# ChristmasTree.net
KiCad netlist of a schematic drawn in Altium Designer
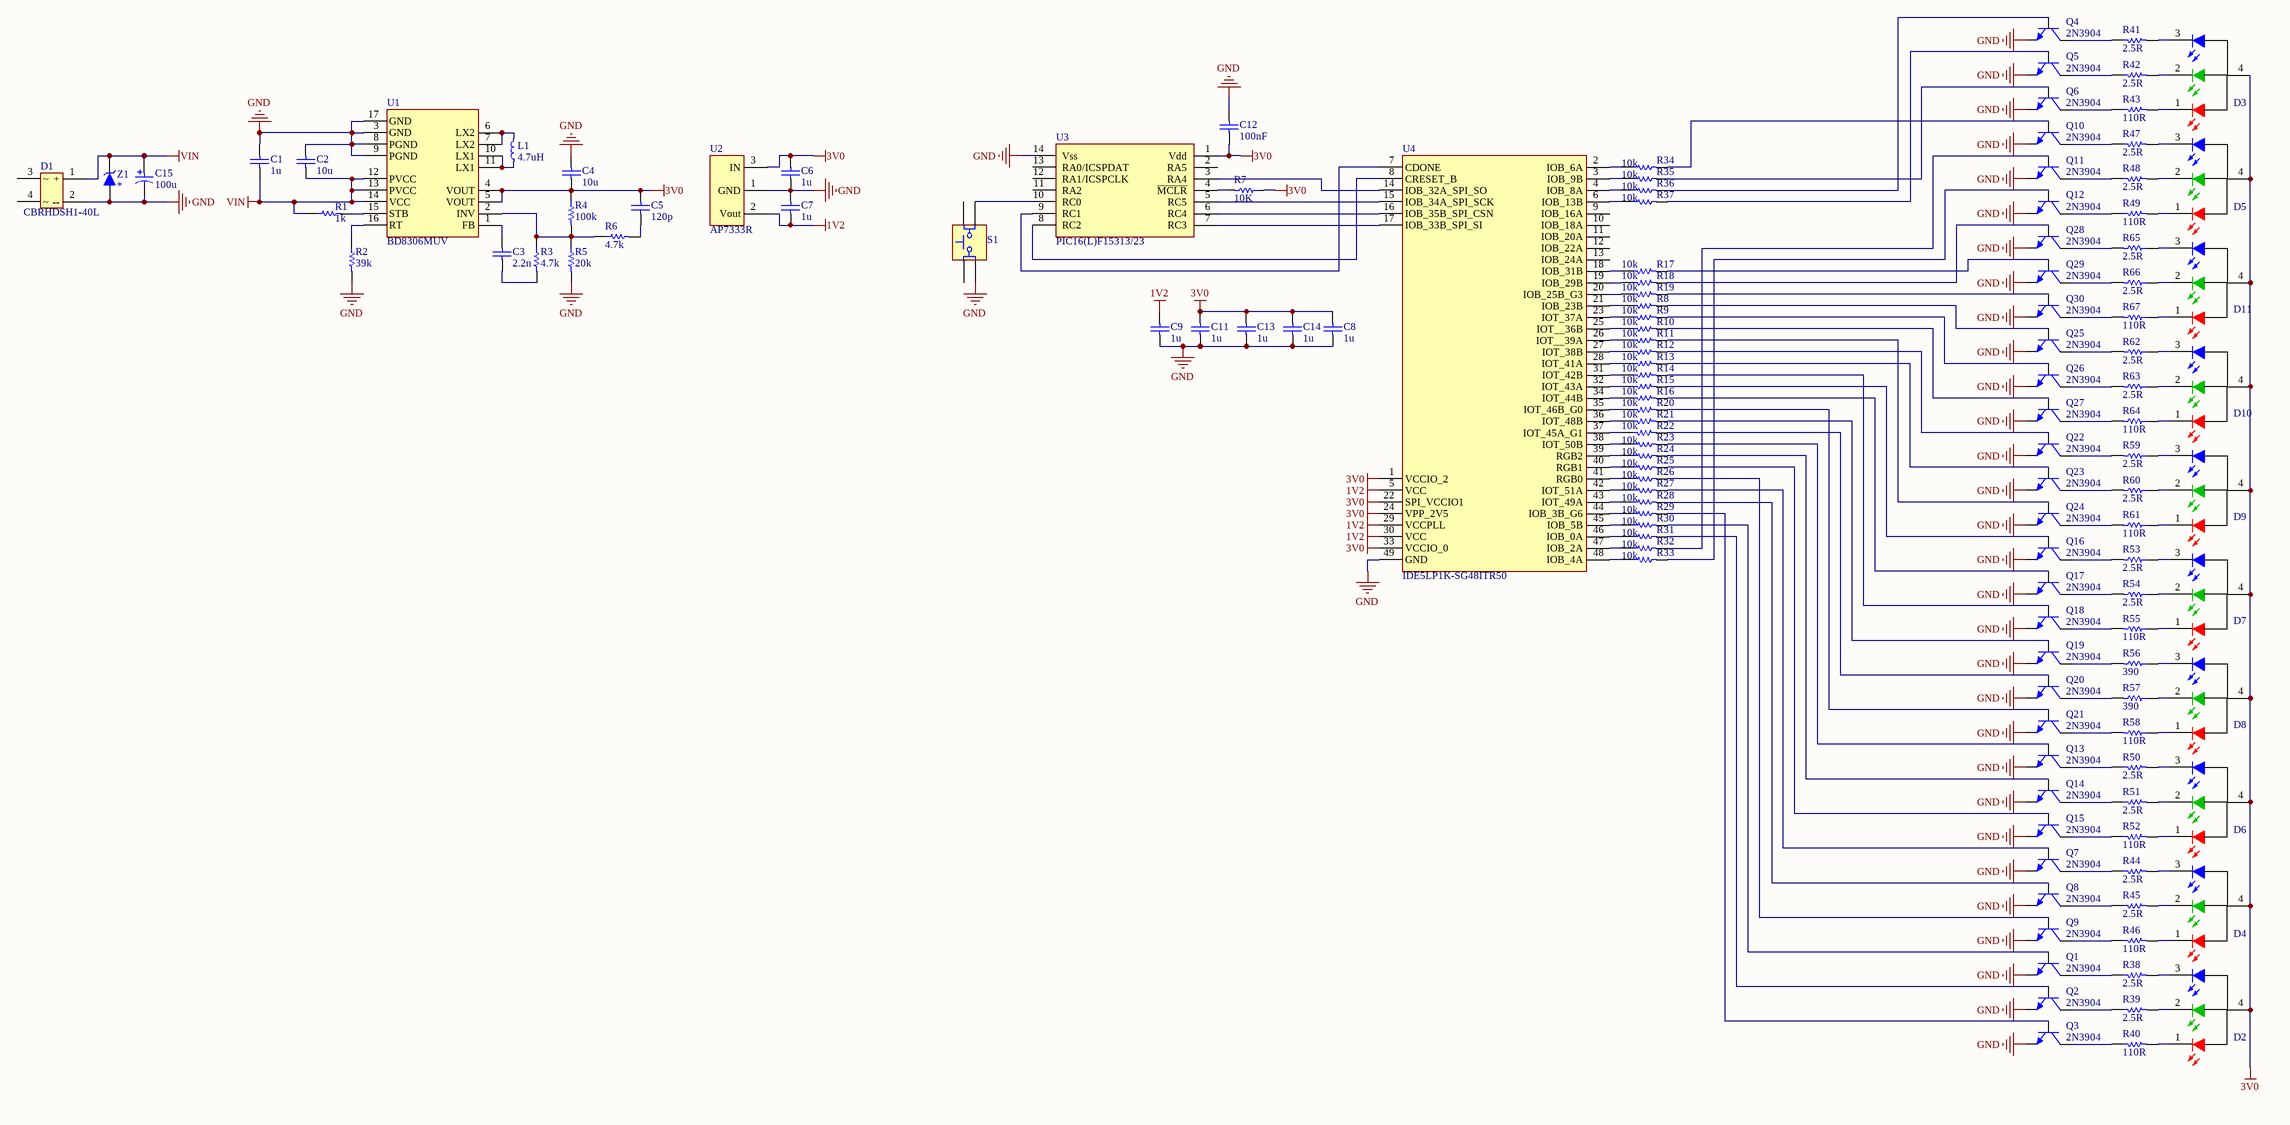
[diagram p0: ChristmasTree.SchDoc]

(export (version "E")
  (design (tool "Eeschema 10.0.6"))
  (components
    (comp (ref "C1")
      (value "1u")
      (footprint "CAP 0603_N")
      (description "CAP, CER")
      (libsource (lib "Passive Components") (part "-Cap Non-Pol"))
    )
    (comp (ref "C2")
      (value "10u")
      (footprint "CAP 0805_N")
      (description "CAP, CER")
      (libsource (lib "Passive Components") (part "-Cap Non-Pol"))
    )
    (comp (ref "C3")
      (value "2.2n")
      (footprint "CAP 0603_N")
      (description "CAP, CER")
      (libsource (lib "Passive Components") (part "-Cap Non-Pol"))
    )
    (comp (ref "C4")
      (value "10u")
      (footprint "CAP 0805_N")
      (description "CAP, CER")
      (libsource (lib "Passive Components") (part "-Cap Non-Pol"))
    )
    (comp (ref "C5")
      (value "120p")
      (footprint "CAP 0603_N")
      (description "CAP, CER")
      (libsource (lib "Passive Components") (part "-Cap Non-Pol"))
    )
    (comp (ref "C6")
      (value "1u")
      (footprint "CAP 0603_N")
      (description "CAP, CER")
      (libsource (lib "Passive Components") (part "-Cap Non-Pol"))
    )
    (comp (ref "C7")
      (value "1u")
      (footprint "CAP 0603_N")
      (description "CAP, CER")
      (libsource (lib "Passive Components") (part "-Cap Non-Pol"))
    )
    (comp (ref "C8")
      (value "1u")
      (footprint "CAP 0603_N")
      (description "CAP, CER")
      (libsource (lib "Passive Components") (part "-Cap Non-Pol"))
    )
    (comp (ref "C9")
      (value "1u")
      (footprint "CAP 0805_N")
      (description "CAP, CER")
      (libsource (lib "Passive Components") (part "-Cap Non-Pol"))
    )
    (comp (ref "C11")
      (value "1u")
      (footprint "CAP 0603_N")
      (description "CAP, CER")
      (libsource (lib "Passive Components") (part "-Cap Non-Pol"))
    )
    (comp (ref "C12")
      (value "100nF")
      (footprint "CAP 0805_N")
      (description "CAP, CER")
      (libsource (lib "Passive Components") (part "-Cap Non-Pol"))
    )
    (comp (ref "C13")
      (value "1u")
      (footprint "CAP 0603_N")
      (description "CAP, CER")
      (libsource (lib "Passive Components") (part "-Cap Non-Pol"))
    )
    (comp (ref "C14")
      (value "1u")
      (footprint "CAP 0603_N")
      (description "CAP, CER")
      (libsource (lib "Passive Components") (part "-Cap Non-Pol"))
    )
    (comp (ref "C15")
      (value "100u")
      (footprint "SMD CAP-6.3X7.7MM-A1K2")
      (description "CAP, ALUM, A1K2")
      (libsource (lib "Passive Components") (part "-Cap Aluminum"))
    )
    (comp (ref "D1")
      (value "CBRHDSH1-40L")
      (footprint "HDDIP(Rectifier)")
      (libsource (lib "A_Semi") (part "CBRHDSH1-40L"))
    )
    (comp (ref "D2")
      (value "RGB LED Common Anode")
      (footprint "LED LTST-C19HE1WT")
      (libsource (lib "Austin_Components") (part "RGB LED Common Anode"))
    )
    (comp (ref "D3")
      (value "RGB LED Common Anode")
      (footprint "LED LTST-C19HE1WT")
      (libsource (lib "Austin_Components") (part "RGB LED Common Anode"))
    )
    (comp (ref "D4")
      (value "RGB LED Common Anode")
      (footprint "LED LTST-C19HE1WT")
      (libsource (lib "Austin_Components") (part "RGB LED Common Anode"))
    )
    (comp (ref "D5")
      (value "RGB LED Common Anode")
      (footprint "LED LTST-C19HE1WT")
      (libsource (lib "Austin_Components") (part "RGB LED Common Anode"))
    )
    (comp (ref "D6")
      (value "RGB LED Common Anode")
      (footprint "LED LTST-C19HE1WT")
      (libsource (lib "Austin_Components") (part "RGB LED Common Anode"))
    )
    (comp (ref "D7")
      (value "RGB LED Common Anode")
      (footprint "LED LTST-C19HE1WT")
      (libsource (lib "Austin_Components") (part "RGB LED Common Anode"))
    )
    (comp (ref "D8")
      (value "RGB LED Common Anode")
      (footprint "LED LTST-C19HE1WT")
      (libsource (lib "Austin_Components") (part "RGB LED Common Anode"))
    )
    (comp (ref "D9")
      (value "RGB LED Common Anode")
      (footprint "LED LTST-C19HE1WT")
      (libsource (lib "Austin_Components") (part "RGB LED Common Anode"))
    )
    (comp (ref "D10")
      (value "RGB LED Common Anode")
      (footprint "LED LTST-C19HE1WT")
      (libsource (lib "Austin_Components") (part "RGB LED Common Anode"))
    )
    (comp (ref "D11")
      (value "RGB LED Common Anode")
      (footprint "LED LTST-C19HE1WT")
      (libsource (lib "Austin_Components") (part "RGB LED Common Anode"))
    )
    (comp (ref "L1")
      (value "4.7uH")
      (footprint "INDC2520X12N")
      (description "IND")
      (libsource (lib "A_Passive") (part "-Inductor"))
    )
    (comp (ref "Q1")
      (value "2N3904")
      (footprint "SOT95P245X110-3N")
      (description "NPN General Purpose Amplifier")
      (fields (field (name "PUBLISHER") "Altium Limited"))
      (libsource (lib "Austin_Components") (part "2N3904"))
    )
    (comp (ref "Q2")
      (value "2N3904")
      (footprint "SOT95P245X110-3N")
      (description "NPN General Purpose Amplifier")
      (fields (field (name "PUBLISHER") "Altium Limited"))
      (libsource (lib "Austin_Components") (part "2N3904"))
    )
    (comp (ref "Q3")
      (value "2N3904")
      (footprint "SOT95P245X110-3N")
      (description "NPN General Purpose Amplifier")
      (fields (field (name "PUBLISHER") "Altium Limited"))
      (libsource (lib "Austin_Components") (part "2N3904"))
    )
    (comp (ref "Q4")
      (value "2N3904")
      (footprint "SOT95P245X110-3N")
      (description "NPN General Purpose Amplifier")
      (fields (field (name "PUBLISHER") "Altium Limited"))
      (libsource (lib "Austin_Components") (part "2N3904"))
    )
    (comp (ref "Q5")
      (value "2N3904")
      (footprint "SOT95P245X110-3N")
      (description "NPN General Purpose Amplifier")
      (fields (field (name "PUBLISHER") "Altium Limited"))
      (libsource (lib "Austin_Components") (part "2N3904"))
    )
    (comp (ref "Q6")
      (value "2N3904")
      (footprint "SOT95P245X110-3N")
      (description "NPN General Purpose Amplifier")
      (fields (field (name "PUBLISHER") "Altium Limited"))
      (libsource (lib "Austin_Components") (part "2N3904"))
    )
    (comp (ref "Q7")
      (value "2N3904")
      (footprint "SOT95P245X110-3N")
      (description "NPN General Purpose Amplifier")
      (fields (field (name "PUBLISHER") "Altium Limited"))
      (libsource (lib "Austin_Components") (part "2N3904"))
    )
    (comp (ref "Q8")
      (value "2N3904")
      (footprint "SOT95P245X110-3N")
      (description "NPN General Purpose Amplifier")
      (fields (field (name "PUBLISHER") "Altium Limited"))
      (libsource (lib "Austin_Components") (part "2N3904"))
    )
    (comp (ref "Q9")
      (value "2N3904")
      (footprint "SOT95P245X110-3N")
      (description "NPN General Purpose Amplifier")
      (fields (field (name "PUBLISHER") "Altium Limited"))
      (libsource (lib "Austin_Components") (part "2N3904"))
    )
    (comp (ref "Q10")
      (value "2N3904")
      (footprint "SOT95P245X110-3N")
      (description "NPN General Purpose Amplifier")
      (fields (field (name "PUBLISHER") "Altium Limited"))
      (libsource (lib "Austin_Components") (part "2N3904"))
    )
    (comp (ref "Q11")
      (value "2N3904")
      (footprint "SOT95P245X110-3N")
      (description "NPN General Purpose Amplifier")
      (fields (field (name "PUBLISHER") "Altium Limited"))
      (libsource (lib "Austin_Components") (part "2N3904"))
    )
    (comp (ref "Q12")
      (value "2N3904")
      (footprint "SOT95P245X110-3N")
      (description "NPN General Purpose Amplifier")
      (fields (field (name "PUBLISHER") "Altium Limited"))
      (libsource (lib "Austin_Components") (part "2N3904"))
    )
    (comp (ref "Q13")
      (value "2N3904")
      (footprint "SOT95P245X110-3N")
      (description "NPN General Purpose Amplifier")
      (fields (field (name "PUBLISHER") "Altium Limited"))
      (libsource (lib "Austin_Components") (part "2N3904"))
    )
    (comp (ref "Q14")
      (value "2N3904")
      (footprint "SOT95P245X110-3N")
      (description "NPN General Purpose Amplifier")
      (fields (field (name "PUBLISHER") "Altium Limited"))
      (libsource (lib "Austin_Components") (part "2N3904"))
    )
    (comp (ref "Q15")
      (value "2N3904")
      (footprint "SOT95P245X110-3N")
      (description "NPN General Purpose Amplifier")
      (fields (field (name "PUBLISHER") "Altium Limited"))
      (libsource (lib "Austin_Components") (part "2N3904"))
    )
    (comp (ref "Q16")
      (value "2N3904")
      (footprint "SOT95P245X110-3N")
      (description "NPN General Purpose Amplifier")
      (fields (field (name "PUBLISHER") "Altium Limited"))
      (libsource (lib "Austin_Components") (part "2N3904"))
    )
    (comp (ref "Q17")
      (value "2N3904")
      (footprint "SOT95P245X110-3N")
      (description "NPN General Purpose Amplifier")
      (fields (field (name "PUBLISHER") "Altium Limited"))
      (libsource (lib "Austin_Components") (part "2N3904"))
    )
    (comp (ref "Q18")
      (value "2N3904")
      (footprint "SOT95P245X110-3N")
      (description "NPN General Purpose Amplifier")
      (fields (field (name "PUBLISHER") "Altium Limited"))
      (libsource (lib "Austin_Components") (part "2N3904"))
    )
    (comp (ref "Q19")
      (value "2N3904")
      (footprint "SOT95P245X110-3N")
      (description "NPN General Purpose Amplifier")
      (fields (field (name "PUBLISHER") "Altium Limited"))
      (libsource (lib "Austin_Components") (part "2N3904"))
    )
    (comp (ref "Q20")
      (value "2N3904")
      (footprint "SOT95P245X110-3N")
      (description "NPN General Purpose Amplifier")
      (fields (field (name "PUBLISHER") "Altium Limited"))
      (libsource (lib "Austin_Components") (part "2N3904"))
    )
    (comp (ref "Q21")
      (value "2N3904")
      (footprint "SOT95P245X110-3N")
      (description "NPN General Purpose Amplifier")
      (fields (field (name "PUBLISHER") "Altium Limited"))
      (libsource (lib "Austin_Components") (part "2N3904"))
    )
    (comp (ref "Q22")
      (value "2N3904")
      (footprint "SOT95P245X110-3N")
      (description "NPN General Purpose Amplifier")
      (fields (field (name "PUBLISHER") "Altium Limited"))
      (libsource (lib "Austin_Components") (part "2N3904"))
    )
    (comp (ref "Q23")
      (value "2N3904")
      (footprint "SOT95P245X110-3N")
      (description "NPN General Purpose Amplifier")
      (fields (field (name "PUBLISHER") "Altium Limited"))
      (libsource (lib "Austin_Components") (part "2N3904"))
    )
    (comp (ref "Q24")
      (value "2N3904")
      (footprint "SOT95P245X110-3N")
      (description "NPN General Purpose Amplifier")
      (fields (field (name "PUBLISHER") "Altium Limited"))
      (libsource (lib "Austin_Components") (part "2N3904"))
    )
    (comp (ref "Q25")
      (value "2N3904")
      (footprint "SOT95P245X110-3N")
      (description "NPN General Purpose Amplifier")
      (fields (field (name "PUBLISHER") "Altium Limited"))
      (libsource (lib "Austin_Components") (part "2N3904"))
    )
    (comp (ref "Q26")
      (value "2N3904")
      (footprint "SOT95P245X110-3N")
      (description "NPN General Purpose Amplifier")
      (fields (field (name "PUBLISHER") "Altium Limited"))
      (libsource (lib "Austin_Components") (part "2N3904"))
    )
    (comp (ref "Q27")
      (value "2N3904")
      (footprint "SOT95P245X110-3N")
      (description "NPN General Purpose Amplifier")
      (fields (field (name "PUBLISHER") "Altium Limited"))
      (libsource (lib "Austin_Components") (part "2N3904"))
    )
    (comp (ref "Q28")
      (value "2N3904")
      (footprint "SOT95P245X110-3N")
      (description "NPN General Purpose Amplifier")
      (fields (field (name "PUBLISHER") "Altium Limited"))
      (libsource (lib "Austin_Components") (part "2N3904"))
    )
    (comp (ref "Q29")
      (value "2N3904")
      (footprint "SOT95P245X110-3N")
      (description "NPN General Purpose Amplifier")
      (fields (field (name "PUBLISHER") "Altium Limited"))
      (libsource (lib "Austin_Components") (part "2N3904"))
    )
    (comp (ref "Q30")
      (value "2N3904")
      (footprint "SOT95P245X110-3N")
      (description "NPN General Purpose Amplifier")
      (fields (field (name "PUBLISHER") "Altium Limited"))
      (libsource (lib "Austin_Components") (part "2N3904"))
    )
    (comp (ref "R1")
      (value "1k")
      (footprint "RES 0603_N")
      (description "Resistor")
      (fields (field (name "Comment") "Res") (field (name "PUBLISHER") "Altium Limited"))
      (libsource (lib "Austin_Components") (part "Res"))
    )
    (comp (ref "R2")
      (value "39k")
      (footprint "RES 0603_N")
      (description "Resistor")
      (fields (field (name "Comment") "Res") (field (name "PUBLISHER") "Altium Limited"))
      (libsource (lib "Austin_Components") (part "Res"))
    )
    (comp (ref "R3")
      (value "4.7k")
      (footprint "RES 0603_N")
      (description "Resistor")
      (fields (field (name "Comment") "Res") (field (name "PUBLISHER") "Altium Limited"))
      (libsource (lib "Austin_Components") (part "Res"))
    )
    (comp (ref "R4")
      (value "100k")
      (footprint "RES 0603_N")
      (description "Resistor")
      (fields (field (name "Comment") "Res") (field (name "PUBLISHER") "Altium Limited"))
      (libsource (lib "Austin_Components") (part "Res"))
    )
    (comp (ref "R5")
      (value "20k")
      (footprint "RES 0603_N")
      (description "Resistor")
      (fields (field (name "Comment") "Res") (field (name "PUBLISHER") "Altium Limited"))
      (libsource (lib "Austin_Components") (part "Res"))
    )
    (comp (ref "R6")
      (value "4.7k")
      (footprint "RES 0603_N")
      (description "Resistor")
      (fields (field (name "Comment") "Res") (field (name "PUBLISHER") "Altium Limited"))
      (libsource (lib "Austin_Components") (part "Res"))
    )
    (comp (ref "R7")
      (value "10K")
      (footprint "RES 0603_N")
      (description "RES, SMD")
      (libsource (lib "Passive Components") (part "-Resistor"))
    )
    (comp (ref "R8")
      (value "10k")
      (footprint "RES 0603_N")
      (description "Resistor")
      (fields (field (name "Comment") "Res") (field (name "PUBLISHER") "Altium Limited"))
      (libsource (lib "Austin_Components") (part "Res"))
    )
    (comp (ref "R9")
      (value "10k")
      (footprint "RES 0603_N")
      (description "Resistor")
      (fields (field (name "Comment") "Res") (field (name "PUBLISHER") "Altium Limited"))
      (libsource (lib "Austin_Components") (part "Res"))
    )
    (comp (ref "R10")
      (value "10k")
      (footprint "RES 0603_N")
      (description "Resistor")
      (fields (field (name "Comment") "Res") (field (name "PUBLISHER") "Altium Limited"))
      (libsource (lib "Austin_Components") (part "Res"))
    )
    (comp (ref "R11")
      (value "10k")
      (footprint "RES 0603_N")
      (description "Resistor")
      (fields (field (name "Comment") "Res") (field (name "PUBLISHER") "Altium Limited"))
      (libsource (lib "Austin_Components") (part "Res"))
    )
    (comp (ref "R12")
      (value "10k")
      (footprint "RES 0603_N")
      (description "Resistor")
      (fields (field (name "Comment") "Res") (field (name "PUBLISHER") "Altium Limited"))
      (libsource (lib "Austin_Components") (part "Res"))
    )
    (comp (ref "R13")
      (value "10k")
      (footprint "RES 0603_N")
      (description "Resistor")
      (fields (field (name "Comment") "Res") (field (name "PUBLISHER") "Altium Limited"))
      (libsource (lib "Austin_Components") (part "Res"))
    )
    (comp (ref "R14")
      (value "10k")
      (footprint "RES 0603_N")
      (description "Resistor")
      (fields (field (name "Comment") "Res") (field (name "PUBLISHER") "Altium Limited"))
      (libsource (lib "Austin_Components") (part "Res"))
    )
    (comp (ref "R15")
      (value "10k")
      (footprint "RES 0603_N")
      (description "Resistor")
      (fields (field (name "Comment") "Res") (field (name "PUBLISHER") "Altium Limited"))
      (libsource (lib "Austin_Components") (part "Res"))
    )
    (comp (ref "R16")
      (value "10k")
      (footprint "RES 0603_N")
      (description "Resistor")
      (fields (field (name "Comment") "Res") (field (name "PUBLISHER") "Altium Limited"))
      (libsource (lib "Austin_Components") (part "Res"))
    )
    (comp (ref "R17")
      (value "10k")
      (footprint "RES 0603_N")
      (description "Resistor")
      (fields (field (name "Comment") "Res") (field (name "PUBLISHER") "Altium Limited"))
      (libsource (lib "Austin_Components") (part "Res"))
    )
    (comp (ref "R18")
      (value "10k")
      (footprint "RES 0603_N")
      (description "Resistor")
      (fields (field (name "Comment") "Res") (field (name "PUBLISHER") "Altium Limited"))
      (libsource (lib "Austin_Components") (part "Res"))
    )
    (comp (ref "R19")
      (value "10k")
      (footprint "RES 0603_N")
      (description "Resistor")
      (fields (field (name "Comment") "Res") (field (name "PUBLISHER") "Altium Limited"))
      (libsource (lib "Austin_Components") (part "Res"))
    )
    (comp (ref "R20")
      (value "10k")
      (footprint "RES 0603_N")
      (description "Resistor")
      (fields (field (name "Comment") "Res") (field (name "PUBLISHER") "Altium Limited"))
      (libsource (lib "Austin_Components") (part "Res"))
    )
    (comp (ref "R21")
      (value "10k")
      (footprint "RES 0603_N")
      (description "Resistor")
      (fields (field (name "Comment") "Res") (field (name "PUBLISHER") "Altium Limited"))
      (libsource (lib "Austin_Components") (part "Res"))
    )
    (comp (ref "R22")
      (value "10k")
      (footprint "RES 0603_N")
      (description "Resistor")
      (fields (field (name "Comment") "Res") (field (name "PUBLISHER") "Altium Limited"))
      (libsource (lib "Austin_Components") (part "Res"))
    )
    (comp (ref "R23")
      (value "10k")
      (footprint "RES 0603_N")
      (description "Resistor")
      (fields (field (name "Comment") "Res") (field (name "PUBLISHER") "Altium Limited"))
      (libsource (lib "Austin_Components") (part "Res"))
    )
    (comp (ref "R24")
      (value "10k")
      (footprint "RES 0603_N")
      (description "Resistor")
      (fields (field (name "Comment") "Res") (field (name "PUBLISHER") "Altium Limited"))
      (libsource (lib "Austin_Components") (part "Res"))
    )
    (comp (ref "R25")
      (value "10k")
      (footprint "RES 0603_N")
      (description "Resistor")
      (fields (field (name "Comment") "Res") (field (name "PUBLISHER") "Altium Limited"))
      (libsource (lib "Austin_Components") (part "Res"))
    )
    (comp (ref "R26")
      (value "10k")
      (footprint "RES 0603_N")
      (description "Resistor")
      (fields (field (name "Comment") "Res") (field (name "PUBLISHER") "Altium Limited"))
      (libsource (lib "Austin_Components") (part "Res"))
    )
    (comp (ref "R27")
      (value "10k")
      (footprint "RES 0603_N")
      (description "Resistor")
      (fields (field (name "Comment") "Res") (field (name "PUBLISHER") "Altium Limited"))
      (libsource (lib "Austin_Components") (part "Res"))
    )
    (comp (ref "R28")
      (value "10k")
      (footprint "RES 0603_N")
      (description "Resistor")
      (fields (field (name "Comment") "Res") (field (name "PUBLISHER") "Altium Limited"))
      (libsource (lib "Austin_Components") (part "Res"))
    )
    (comp (ref "R29")
      (value "10k")
      (footprint "RES 0603_N")
      (description "Resistor")
      (fields (field (name "Comment") "Res") (field (name "PUBLISHER") "Altium Limited"))
      (libsource (lib "Austin_Components") (part "Res"))
    )
    (comp (ref "R30")
      (value "10k")
      (footprint "RES 0603_N")
      (description "Resistor")
      (fields (field (name "Comment") "Res") (field (name "PUBLISHER") "Altium Limited"))
      (libsource (lib "Austin_Components") (part "Res"))
    )
    (comp (ref "R31")
      (value "10k")
      (footprint "RES 0603_N")
      (description "Resistor")
      (fields (field (name "Comment") "Res") (field (name "PUBLISHER") "Altium Limited"))
      (libsource (lib "Austin_Components") (part "Res"))
    )
    (comp (ref "R32")
      (value "10k")
      (footprint "RES 0603_N")
      (description "Resistor")
      (fields (field (name "Comment") "Res") (field (name "PUBLISHER") "Altium Limited"))
      (libsource (lib "Austin_Components") (part "Res"))
    )
    (comp (ref "R33")
      (value "10k")
      (footprint "RES 0603_N")
      (description "Resistor")
      (fields (field (name "Comment") "Res") (field (name "PUBLISHER") "Altium Limited"))
      (libsource (lib "Austin_Components") (part "Res"))
    )
    (comp (ref "R34")
      (value "10k")
      (footprint "RES 0603_N")
      (description "Resistor")
      (fields (field (name "Comment") "Res") (field (name "PUBLISHER") "Altium Limited"))
      (libsource (lib "Austin_Components") (part "Res"))
    )
    (comp (ref "R35")
      (value "10k")
      (footprint "RES 0603_N")
      (description "Resistor")
      (fields (field (name "Comment") "Res") (field (name "PUBLISHER") "Altium Limited"))
      (libsource (lib "Austin_Components") (part "Res"))
    )
    (comp (ref "R36")
      (value "10k")
      (footprint "RES 0603_N")
      (description "Resistor")
      (fields (field (name "Comment") "Res") (field (name "PUBLISHER") "Altium Limited"))
      (libsource (lib "Austin_Components") (part "Res"))
    )
    (comp (ref "R37")
      (value "10k")
      (footprint "RES 0603_N")
      (description "Resistor")
      (fields (field (name "Comment") "Res") (field (name "PUBLISHER") "Altium Limited"))
      (libsource (lib "Austin_Components") (part "Res"))
    )
    (comp (ref "R38")
      (value "2.5R")
      (footprint "RES 0603_N")
      (description "Resistor")
      (fields (field (name "Comment") "Res") (field (name "PUBLISHER") "Altium Limited"))
      (libsource (lib "Austin_Components") (part "Res"))
    )
    (comp (ref "R39")
      (value "2.5R")
      (footprint "RES 0603_N")
      (description "Resistor")
      (fields (field (name "Comment") "Res") (field (name "PUBLISHER") "Altium Limited"))
      (libsource (lib "Austin_Components") (part "Res"))
    )
    (comp (ref "R40")
      (value "110R")
      (footprint "RES 0603_N")
      (description "Resistor")
      (fields (field (name "Comment") "Res") (field (name "PUBLISHER") "Altium Limited"))
      (libsource (lib "Austin_Components") (part "Res"))
    )
    (comp (ref "R41")
      (value "2.5R")
      (footprint "RES 0603_N")
      (description "Resistor")
      (fields (field (name "Comment") "Res") (field (name "PUBLISHER") "Altium Limited"))
      (libsource (lib "Austin_Components") (part "Res"))
    )
    (comp (ref "R42")
      (value "2.5R")
      (footprint "RES 0603_N")
      (description "Resistor")
      (fields (field (name "Comment") "Res") (field (name "PUBLISHER") "Altium Limited"))
      (libsource (lib "Austin_Components") (part "Res"))
    )
    (comp (ref "R43")
      (value "110R")
      (footprint "RES 0603_N")
      (description "Resistor")
      (fields (field (name "Comment") "Res") (field (name "PUBLISHER") "Altium Limited"))
      (libsource (lib "Austin_Components") (part "Res"))
    )
    (comp (ref "R44")
      (value "2.5R")
      (footprint "RES 0603_N")
      (description "Resistor")
      (fields (field (name "Comment") "Res") (field (name "PUBLISHER") "Altium Limited"))
      (libsource (lib "Austin_Components") (part "Res"))
    )
    (comp (ref "R45")
      (value "2.5R")
      (footprint "RES 0603_N")
      (description "Resistor")
      (fields (field (name "Comment") "Res") (field (name "PUBLISHER") "Altium Limited"))
      (libsource (lib "Austin_Components") (part "Res"))
    )
    (comp (ref "R46")
      (value "110R")
      (footprint "RES 0603_N")
      (description "Resistor")
      (fields (field (name "Comment") "Res") (field (name "PUBLISHER") "Altium Limited"))
      (libsource (lib "Austin_Components") (part "Res"))
    )
    (comp (ref "R47")
      (value "2.5R")
      (footprint "RES 0603_N")
      (description "Resistor")
      (fields (field (name "Comment") "Res") (field (name "PUBLISHER") "Altium Limited"))
      (libsource (lib "Austin_Components") (part "Res"))
    )
    (comp (ref "R48")
      (value "2.5R")
      (footprint "RES 0603_N")
      (description "Resistor")
      (fields (field (name "Comment") "Res") (field (name "PUBLISHER") "Altium Limited"))
      (libsource (lib "Austin_Components") (part "Res"))
    )
    (comp (ref "R49")
      (value "110R")
      (footprint "RES 0603_N")
      (description "Resistor")
      (fields (field (name "Comment") "Res") (field (name "PUBLISHER") "Altium Limited"))
      (libsource (lib "Austin_Components") (part "Res"))
    )
    (comp (ref "R50")
      (value "2.5R")
      (footprint "RES 0603_N")
      (description "Resistor")
      (fields (field (name "Comment") "Res") (field (name "PUBLISHER") "Altium Limited"))
      (libsource (lib "Austin_Components") (part "Res"))
    )
    (comp (ref "R51")
      (value "2.5R")
      (footprint "RES 0603_N")
      (description "Resistor")
      (fields (field (name "Comment") "Res") (field (name "PUBLISHER") "Altium Limited"))
      (libsource (lib "Austin_Components") (part "Res"))
    )
    (comp (ref "R52")
      (value "110R")
      (footprint "RES 0603_N")
      (description "Resistor")
      (fields (field (name "Comment") "Res") (field (name "PUBLISHER") "Altium Limited"))
      (libsource (lib "Austin_Components") (part "Res"))
    )
    (comp (ref "R53")
      (value "2.5R")
      (footprint "RES 0603_N")
      (description "Resistor")
      (fields (field (name "Comment") "Res") (field (name "PUBLISHER") "Altium Limited"))
      (libsource (lib "Austin_Components") (part "Res"))
    )
    (comp (ref "R54")
      (value "2.5R")
      (footprint "RES 0603_N")
      (description "Resistor")
      (fields (field (name "Comment") "Res") (field (name "PUBLISHER") "Altium Limited"))
      (libsource (lib "Austin_Components") (part "Res"))
    )
    (comp (ref "R55")
      (value "110R")
      (footprint "RES 0603_N")
      (description "Resistor")
      (fields (field (name "Comment") "Res") (field (name "PUBLISHER") "Altium Limited"))
      (libsource (lib "Austin_Components") (part "Res"))
    )
    (comp (ref "R56")
      (value "390")
      (footprint "RES 0603_N")
      (description "Resistor")
      (fields (field (name "Comment") "Res") (field (name "PUBLISHER") "Altium Limited"))
      (libsource (lib "Austin_Components") (part "Res"))
    )
    (comp (ref "R57")
      (value "390")
      (footprint "RES 0603_N")
      (description "Resistor")
      (fields (field (name "Comment") "Res") (field (name "PUBLISHER") "Altium Limited"))
      (libsource (lib "Austin_Components") (part "Res"))
    )
    (comp (ref "R58")
      (value "110R")
      (footprint "RES 0603_N")
      (description "Resistor")
      (fields (field (name "Comment") "Res") (field (name "PUBLISHER") "Altium Limited"))
      (libsource (lib "Austin_Components") (part "Res"))
    )
    (comp (ref "R59")
      (value "2.5R")
      (footprint "RES 0603_N")
      (description "Resistor")
      (fields (field (name "Comment") "Res") (field (name "PUBLISHER") "Altium Limited"))
      (libsource (lib "Austin_Components") (part "Res"))
    )
    (comp (ref "R60")
      (value "2.5R")
      (footprint "RES 0603_N")
      (description "Resistor")
      (fields (field (name "Comment") "Res") (field (name "PUBLISHER") "Altium Limited"))
      (libsource (lib "Austin_Components") (part "Res"))
    )
    (comp (ref "R61")
      (value "110R")
      (footprint "RES 0603_N")
      (description "Resistor")
      (fields (field (name "Comment") "Res") (field (name "PUBLISHER") "Altium Limited"))
      (libsource (lib "Austin_Components") (part "Res"))
    )
    (comp (ref "R62")
      (value "2.5R")
      (footprint "RES 0603_N")
      (description "Resistor")
      (fields (field (name "Comment") "Res") (field (name "PUBLISHER") "Altium Limited"))
      (libsource (lib "Austin_Components") (part "Res"))
    )
    (comp (ref "R63")
      (value "2.5R")
      (footprint "RES 0603_N")
      (description "Resistor")
      (fields (field (name "Comment") "Res") (field (name "PUBLISHER") "Altium Limited"))
      (libsource (lib "Austin_Components") (part "Res"))
    )
    (comp (ref "R64")
      (value "110R")
      (footprint "RES 0603_N")
      (description "Resistor")
      (fields (field (name "Comment") "Res") (field (name "PUBLISHER") "Altium Limited"))
      (libsource (lib "Austin_Components") (part "Res"))
    )
    (comp (ref "R65")
      (value "2.5R")
      (footprint "RES 0603_N")
      (description "Resistor")
      (fields (field (name "Comment") "Res") (field (name "PUBLISHER") "Altium Limited"))
      (libsource (lib "Austin_Components") (part "Res"))
    )
    (comp (ref "R66")
      (value "2.5R")
      (footprint "RES 0603_N")
      (description "Resistor")
      (fields (field (name "Comment") "Res") (field (name "PUBLISHER") "Altium Limited"))
      (libsource (lib "Austin_Components") (part "Res"))
    )
    (comp (ref "R67")
      (value "110R")
      (footprint "RES 0603_N")
      (description "Resistor")
      (fields (field (name "Comment") "Res") (field (name "PUBLISHER") "Altium Limited"))
      (libsource (lib "Austin_Components") (part "Res"))
    )
    (comp (ref "S1")
      (value "SW Tactile")
      (footprint "SW-TACT-SMD-6060")
      (description "SPST, Normally Open, Push Button")
      (libsource (lib "Electromechanical") (part "SW-NO (PTS645SM43SMTR 92 LFS)"))
    )
    (comp (ref "U1")
      (value "BD8306MUV")
      (footprint "QFN50P300X300X100_HS-17N")
      (libsource (lib "A_Semi") (part "BD8306MUV"))
    )
    (comp (ref "U2")
      (value "AP7333R")
      (footprint "SOT95P245X110-3N")
      (libsource (lib "A_Semi") (part "AP7333R"))
    )
    (comp (ref "U3")
      (value "PIC16(L)F15313/23")
      (footprint "SOIC14")
      (libsource (lib "A_Semi") (part "PIC16(L)F15313/23"))
    )
    (comp (ref "U4")
      (value "IDE5LP1K-SG48ITR50")
      (footprint "QFN50P700X700X85_HS-49M")
      (libsource (lib "A_Semi") (part "IDE5LP1K-SG48ITR50"))
    )
    (comp (ref "Z1")
      (value "*")
      (footprint "SOD-123-K1A2")
      (description "2 Pin Zener K1A2")
      (fields (field (name "ALTIUM_VALUE") "*"))
      (libsource (lib "Semiconductors") (part "-Diode Zener K1A2"))
    )
  )
  (nets
    (net (code "1") (name "1V2") (class "Default")
      (node (ref "C7") (pin "2") (pinfunction "2_2") (pintype "passive"))
      (node (ref "C9") (pin "1") (pinfunction "1_1") (pintype "passive"))
      (node (ref "U2") (pin "2") (pinfunction "Vout_2") (pintype "passive"))
      (node (ref "U4") (pin "29") (pinfunction "VCCPLL_29") (pintype "passive"))
      (node (ref "U4") (pin "30") (pinfunction "VCC_30") (pintype "passive"))
      (node (ref "U4") (pin "5") (pinfunction "VCC_5") (pintype "passive"))
    )
    (net (code "2") (name "3V0") (class "Default")
      (node (ref "C11") (pin "1") (pinfunction "1_1") (pintype "passive"))
      (node (ref "C12") (pin "1") (pinfunction "1_1") (pintype "passive"))
      (node (ref "C13") (pin "1") (pinfunction "1_1") (pintype "passive"))
      (node (ref "C14") (pin "1") (pinfunction "1_1") (pintype "passive"))
      (node (ref "C4") (pin "2") (pinfunction "2_2") (pintype "passive"))
      (node (ref "C5") (pin "2") (pinfunction "2_2") (pintype "passive"))
      (node (ref "C6") (pin "1") (pinfunction "1_1") (pintype "passive"))
      (node (ref "C8") (pin "1") (pinfunction "1_1") (pintype "passive"))
      (node (ref "D10") (pin "4") (pinfunction "A_4") (pintype "passive"))
      (node (ref "D11") (pin "4") (pinfunction "A_4") (pintype "passive"))
      (node (ref "D2") (pin "4") (pinfunction "A_4") (pintype "passive"))
      (node (ref "D3") (pin "4") (pinfunction "A_4") (pintype "passive"))
      (node (ref "D4") (pin "4") (pinfunction "A_4") (pintype "passive"))
      (node (ref "D5") (pin "4") (pinfunction "A_4") (pintype "passive"))
      (node (ref "D6") (pin "4") (pinfunction "A_4") (pintype "passive"))
      (node (ref "D7") (pin "4") (pinfunction "A_4") (pintype "passive"))
      (node (ref "D8") (pin "4") (pinfunction "A_4") (pintype "passive"))
      (node (ref "D9") (pin "4") (pinfunction "A_4") (pintype "passive"))
      (node (ref "R4") (pin "1") (pinfunction "1_1") (pintype "passive"))
      (node (ref "R7") (pin "1") (pinfunction "1_1") (pintype "passive"))
      (node (ref "U1") (pin "4") (pinfunction "VOUT_4") (pintype "passive"))
      (node (ref "U1") (pin "5") (pinfunction "VOUT_5") (pintype "passive"))
      (node (ref "U2") (pin "3") (pinfunction "IN_3") (pintype "passive"))
      (node (ref "U3") (pin "1") (pinfunction "Vdd_1") (pintype "passive"))
      (node (ref "U4") (pin "1") (pinfunction "VCCIO_2_1") (pintype "passive"))
      (node (ref "U4") (pin "22") (pinfunction "SPI_VCCIO1_22") (pintype "passive"))
      (node (ref "U4") (pin "24") (pinfunction "VPP_2V5_24") (pintype "passive"))
      (node (ref "U4") (pin "33") (pinfunction "VCCIO_0_33") (pintype "passive"))
    )
    (net (code "3") (name "GND") (class "Default")
      (node (ref "C1") (pin "2") (pinfunction "2_2") (pintype "passive"))
      (node (ref "C11") (pin "2") (pinfunction "2_2") (pintype "passive"))
      (node (ref "C12") (pin "2") (pinfunction "2_2") (pintype "passive"))
      (node (ref "C13") (pin "2") (pinfunction "2_2") (pintype "passive"))
      (node (ref "C14") (pin "2") (pinfunction "2_2") (pintype "passive"))
      (node (ref "C15") (pin "2") (pinfunction "K_2") (pintype "passive"))
      (node (ref "C2") (pin "2") (pinfunction "2_2") (pintype "passive"))
      (node (ref "C4") (pin "1") (pinfunction "1_1") (pintype "passive"))
      (node (ref "C6") (pin "2") (pinfunction "2_2") (pintype "passive"))
      (node (ref "C7") (pin "1") (pinfunction "1_1") (pintype "passive"))
      (node (ref "C8") (pin "2") (pinfunction "2_2") (pintype "passive"))
      (node (ref "C9") (pin "2") (pinfunction "2_2") (pintype "passive"))
      (node (ref "D1") (pin "2") (pinfunction "--_2") (pintype "passive"))
      (node (ref "Q1") (pin "2") (pinfunction "E_2") (pintype "passive"))
      (node (ref "Q10") (pin "2") (pinfunction "E_2") (pintype "passive"))
      (node (ref "Q11") (pin "2") (pinfunction "E_2") (pintype "passive"))
      (node (ref "Q12") (pin "2") (pinfunction "E_2") (pintype "passive"))
      (node (ref "Q13") (pin "2") (pinfunction "E_2") (pintype "passive"))
      (node (ref "Q14") (pin "2") (pinfunction "E_2") (pintype "passive"))
      (node (ref "Q15") (pin "2") (pinfunction "E_2") (pintype "passive"))
      (node (ref "Q16") (pin "2") (pinfunction "E_2") (pintype "passive"))
      (node (ref "Q17") (pin "2") (pinfunction "E_2") (pintype "passive"))
      (node (ref "Q18") (pin "2") (pinfunction "E_2") (pintype "passive"))
      (node (ref "Q19") (pin "2") (pinfunction "E_2") (pintype "passive"))
      (node (ref "Q2") (pin "2") (pinfunction "E_2") (pintype "passive"))
      (node (ref "Q20") (pin "2") (pinfunction "E_2") (pintype "passive"))
      (node (ref "Q21") (pin "2") (pinfunction "E_2") (pintype "passive"))
      (node (ref "Q22") (pin "2") (pinfunction "E_2") (pintype "passive"))
      (node (ref "Q23") (pin "2") (pinfunction "E_2") (pintype "passive"))
      (node (ref "Q24") (pin "2") (pinfunction "E_2") (pintype "passive"))
      (node (ref "Q25") (pin "2") (pinfunction "E_2") (pintype "passive"))
      (node (ref "Q26") (pin "2") (pinfunction "E_2") (pintype "passive"))
      (node (ref "Q27") (pin "2") (pinfunction "E_2") (pintype "passive"))
      (node (ref "Q28") (pin "2") (pinfunction "E_2") (pintype "passive"))
      (node (ref "Q29") (pin "2") (pinfunction "E_2") (pintype "passive"))
      (node (ref "Q3") (pin "2") (pinfunction "E_2") (pintype "passive"))
      (node (ref "Q30") (pin "2") (pinfunction "E_2") (pintype "passive"))
      (node (ref "Q4") (pin "2") (pinfunction "E_2") (pintype "passive"))
      (node (ref "Q5") (pin "2") (pinfunction "E_2") (pintype "passive"))
      (node (ref "Q6") (pin "2") (pinfunction "E_2") (pintype "passive"))
      (node (ref "Q7") (pin "2") (pinfunction "E_2") (pintype "passive"))
      (node (ref "Q8") (pin "2") (pinfunction "E_2") (pintype "passive"))
      (node (ref "Q9") (pin "2") (pinfunction "E_2") (pintype "passive"))
      (node (ref "R2") (pin "2") (pinfunction "2_2") (pintype "passive"))
      (node (ref "R5") (pin "2") (pinfunction "2_2") (pintype "passive"))
      (node (ref "S1") (pin "2") (pinfunction "2_2") (pintype "passive"))
      (node (ref "U1") (pin "17") (pinfunction "GND_17") (pintype "passive"))
      (node (ref "U1") (pin "3") (pinfunction "GND_3") (pintype "passive"))
      (node (ref "U1") (pin "8") (pinfunction "PGND_8") (pintype "passive"))
      (node (ref "U1") (pin "9") (pinfunction "PGND_9") (pintype "passive"))
      (node (ref "U2") (pin "1") (pinfunction "GND_1") (pintype "passive"))
      (node (ref "U3") (pin "14") (pinfunction "Vss_14") (pintype "passive"))
      (node (ref "U4") (pin "49") (pinfunction "GND_49") (pintype "passive"))
      (node (ref "Z1") (pin "2") (pinfunction "A_2") (pintype "passive"))
    )
    (net (code "4") (name "Net-(C3-Pad1)") (class "Default")
      (node (ref "C3") (pin "1") (pinfunction "1_1") (pintype "passive"))
      (node (ref "R3") (pin "2") (pinfunction "2_2") (pintype "passive"))
    )
    (net (code "5") (name "Net-(C5-Pad1)") (class "Default")
      (node (ref "C5") (pin "1") (pinfunction "1_1") (pintype "passive"))
      (node (ref "R6") (pin "2") (pinfunction "2_2") (pintype "passive"))
    )
    (net (code "6") (name "Net-(D2-K-Pad1)") (class "Default")
      (node (ref "D2") (pin "1") (pinfunction "K_1") (pintype "passive"))
      (node (ref "R40") (pin "2") (pinfunction "2_2") (pintype "passive"))
    )
    (net (code "7") (name "Net-(D2-K-Pad2)") (class "Default")
      (node (ref "D2") (pin "2") (pinfunction "K_2") (pintype "passive"))
      (node (ref "R39") (pin "2") (pinfunction "2_2") (pintype "passive"))
    )
    (net (code "8") (name "Net-(D2-K-Pad3)") (class "Default")
      (node (ref "D2") (pin "3") (pinfunction "K_3") (pintype "passive"))
      (node (ref "R38") (pin "2") (pinfunction "2_2") (pintype "passive"))
    )
    (net (code "9") (name "Net-(D3-K-Pad1)") (class "Default")
      (node (ref "D3") (pin "1") (pinfunction "K_1") (pintype "passive"))
      (node (ref "R43") (pin "2") (pinfunction "2_2") (pintype "passive"))
    )
    (net (code "10") (name "Net-(D3-K-Pad2)") (class "Default")
      (node (ref "D3") (pin "2") (pinfunction "K_2") (pintype "passive"))
      (node (ref "R42") (pin "2") (pinfunction "2_2") (pintype "passive"))
    )
    (net (code "11") (name "Net-(D3-K-Pad3)") (class "Default")
      (node (ref "D3") (pin "3") (pinfunction "K_3") (pintype "passive"))
      (node (ref "R41") (pin "2") (pinfunction "2_2") (pintype "passive"))
    )
    (net (code "12") (name "Net-(D4-K-Pad1)") (class "Default")
      (node (ref "D4") (pin "1") (pinfunction "K_1") (pintype "passive"))
      (node (ref "R46") (pin "2") (pinfunction "2_2") (pintype "passive"))
    )
    (net (code "13") (name "Net-(D4-K-Pad2)") (class "Default")
      (node (ref "D4") (pin "2") (pinfunction "K_2") (pintype "passive"))
      (node (ref "R45") (pin "2") (pinfunction "2_2") (pintype "passive"))
    )
    (net (code "14") (name "Net-(D4-K-Pad3)") (class "Default")
      (node (ref "D4") (pin "3") (pinfunction "K_3") (pintype "passive"))
      (node (ref "R44") (pin "2") (pinfunction "2_2") (pintype "passive"))
    )
    (net (code "15") (name "Net-(D5-K-Pad1)") (class "Default")
      (node (ref "D5") (pin "1") (pinfunction "K_1") (pintype "passive"))
      (node (ref "R49") (pin "2") (pinfunction "2_2") (pintype "passive"))
    )
    (net (code "16") (name "Net-(D5-K-Pad2)") (class "Default")
      (node (ref "D5") (pin "2") (pinfunction "K_2") (pintype "passive"))
      (node (ref "R48") (pin "2") (pinfunction "2_2") (pintype "passive"))
    )
    (net (code "17") (name "Net-(D5-K-Pad3)") (class "Default")
      (node (ref "D5") (pin "3") (pinfunction "K_3") (pintype "passive"))
      (node (ref "R47") (pin "2") (pinfunction "2_2") (pintype "passive"))
    )
    (net (code "18") (name "Net-(D6-K-Pad1)") (class "Default")
      (node (ref "D6") (pin "1") (pinfunction "K_1") (pintype "passive"))
      (node (ref "R52") (pin "2") (pinfunction "2_2") (pintype "passive"))
    )
    (net (code "19") (name "Net-(D6-K-Pad2)") (class "Default")
      (node (ref "D6") (pin "2") (pinfunction "K_2") (pintype "passive"))
      (node (ref "R51") (pin "2") (pinfunction "2_2") (pintype "passive"))
    )
    (net (code "20") (name "Net-(D6-K-Pad3)") (class "Default")
      (node (ref "D6") (pin "3") (pinfunction "K_3") (pintype "passive"))
      (node (ref "R50") (pin "2") (pinfunction "2_2") (pintype "passive"))
    )
    (net (code "21") (name "Net-(D7-K-Pad1)") (class "Default")
      (node (ref "D7") (pin "1") (pinfunction "K_1") (pintype "passive"))
      (node (ref "R55") (pin "1") (pinfunction "1_1") (pintype "passive"))
    )
    (net (code "22") (name "Net-(D7-K-Pad2)") (class "Default")
      (node (ref "D7") (pin "2") (pinfunction "K_2") (pintype "passive"))
      (node (ref "R54") (pin "1") (pinfunction "1_1") (pintype "passive"))
    )
    (net (code "23") (name "Net-(D7-K-Pad3)") (class "Default")
      (node (ref "D7") (pin "3") (pinfunction "K_3") (pintype "passive"))
      (node (ref "R53") (pin "1") (pinfunction "1_1") (pintype "passive"))
    )
    (net (code "24") (name "Net-(D8-K-Pad1)") (class "Default")
      (node (ref "D8") (pin "1") (pinfunction "K_1") (pintype "passive"))
      (node (ref "R58") (pin "1") (pinfunction "1_1") (pintype "passive"))
    )
    (net (code "25") (name "Net-(D8-K-Pad2)") (class "Default")
      (node (ref "D8") (pin "2") (pinfunction "K_2") (pintype "passive"))
      (node (ref "R57") (pin "1") (pinfunction "1_1") (pintype "passive"))
    )
    (net (code "26") (name "Net-(D8-K-Pad3)") (class "Default")
      (node (ref "D8") (pin "3") (pinfunction "K_3") (pintype "passive"))
      (node (ref "R56") (pin "1") (pinfunction "1_1") (pintype "passive"))
    )
    (net (code "27") (name "Net-(D9-K-Pad1)") (class "Default")
      (node (ref "D9") (pin "1") (pinfunction "K_1") (pintype "passive"))
      (node (ref "R61") (pin "1") (pinfunction "1_1") (pintype "passive"))
    )
    (net (code "28") (name "Net-(D9-K-Pad2)") (class "Default")
      (node (ref "D9") (pin "2") (pinfunction "K_2") (pintype "passive"))
      (node (ref "R60") (pin "1") (pinfunction "1_1") (pintype "passive"))
    )
    (net (code "29") (name "Net-(D9-K-Pad3)") (class "Default")
      (node (ref "D9") (pin "3") (pinfunction "K_3") (pintype "passive"))
      (node (ref "R59") (pin "1") (pinfunction "1_1") (pintype "passive"))
    )
    (net (code "30") (name "Net-(D10-K-Pad1)") (class "Default")
      (node (ref "D10") (pin "1") (pinfunction "K_1") (pintype "passive"))
      (node (ref "R64") (pin "1") (pinfunction "1_1") (pintype "passive"))
    )
    (net (code "31") (name "Net-(D10-K-Pad2)") (class "Default")
      (node (ref "D10") (pin "2") (pinfunction "K_2") (pintype "passive"))
      (node (ref "R63") (pin "1") (pinfunction "1_1") (pintype "passive"))
    )
    (net (code "32") (name "Net-(D10-K-Pad3)") (class "Default")
      (node (ref "D10") (pin "3") (pinfunction "K_3") (pintype "passive"))
      (node (ref "R62") (pin "1") (pinfunction "1_1") (pintype "passive"))
    )
    (net (code "33") (name "Net-(D11-K-Pad1)") (class "Default")
      (node (ref "D11") (pin "1") (pinfunction "K_1") (pintype "passive"))
      (node (ref "R67") (pin "1") (pinfunction "1_1") (pintype "passive"))
    )
    (net (code "34") (name "Net-(D11-K-Pad2)") (class "Default")
      (node (ref "D11") (pin "2") (pinfunction "K_2") (pintype "passive"))
      (node (ref "R66") (pin "1") (pinfunction "1_1") (pintype "passive"))
    )
    (net (code "35") (name "Net-(D11-K-Pad3)") (class "Default")
      (node (ref "D11") (pin "3") (pinfunction "K_3") (pintype "passive"))
      (node (ref "R65") (pin "1") (pinfunction "1_1") (pintype "passive"))
    )
    (net (code "36") (name "Net-(L1-Pad1)") (class "Default")
      (node (ref "L1") (pin "1") (pinfunction "1_1") (pintype "passive"))
      (node (ref "U1") (pin "10") (pinfunction "LX1_10") (pintype "passive"))
      (node (ref "U1") (pin "11") (pinfunction "LX1_11") (pintype "passive"))
    )
    (net (code "37") (name "Net-(L1-Pad2)") (class "Default")
      (node (ref "L1") (pin "2") (pinfunction "2_2") (pintype "passive"))
      (node (ref "U1") (pin "6") (pinfunction "LX2_6") (pintype "passive"))
      (node (ref "U1") (pin "7") (pinfunction "LX2_7") (pintype "passive"))
    )
    (net (code "38") (name "Net-(Q1-B)") (class "Default")
      (node (ref "Q1") (pin "1") (pinfunction "B_1") (pintype "passive"))
      (node (ref "R30") (pin "2") (pinfunction "2_2") (pintype "passive"))
    )
    (net (code "39") (name "Net-(Q1-C)") (class "Default")
      (node (ref "Q1") (pin "3") (pinfunction "C_3") (pintype "passive"))
      (node (ref "R38") (pin "1") (pinfunction "1_1") (pintype "passive"))
    )
    (net (code "40") (name "Net-(Q2-B)") (class "Default")
      (node (ref "Q2") (pin "1") (pinfunction "B_1") (pintype "passive"))
      (node (ref "R31") (pin "2") (pinfunction "2_2") (pintype "passive"))
    )
    (net (code "41") (name "Net-(Q2-C)") (class "Default")
      (node (ref "Q2") (pin "3") (pinfunction "C_3") (pintype "passive"))
      (node (ref "R39") (pin "1") (pinfunction "1_1") (pintype "passive"))
    )
    (net (code "42") (name "Net-(Q3-B)") (class "Default")
      (node (ref "Q3") (pin "1") (pinfunction "B_1") (pintype "passive"))
      (node (ref "R29") (pin "2") (pinfunction "2_2") (pintype "passive"))
    )
    (net (code "43") (name "Net-(Q3-C)") (class "Default")
      (node (ref "Q3") (pin "3") (pinfunction "C_3") (pintype "passive"))
      (node (ref "R40") (pin "1") (pinfunction "1_1") (pintype "passive"))
    )
    (net (code "44") (name "Net-(Q4-B)") (class "Default")
      (node (ref "Q4") (pin "1") (pinfunction "B_1") (pintype "passive"))
      (node (ref "R36") (pin "2") (pinfunction "2_2") (pintype "passive"))
    )
    (net (code "45") (name "Net-(Q4-C)") (class "Default")
      (node (ref "Q4") (pin "3") (pinfunction "C_3") (pintype "passive"))
      (node (ref "R41") (pin "1") (pinfunction "1_1") (pintype "passive"))
    )
    (net (code "46") (name "Net-(Q5-B)") (class "Default")
      (node (ref "Q5") (pin "1") (pinfunction "B_1") (pintype "passive"))
      (node (ref "R37") (pin "2") (pinfunction "2_2") (pintype "passive"))
    )
    (net (code "47") (name "Net-(Q5-C)") (class "Default")
      (node (ref "Q5") (pin "3") (pinfunction "C_3") (pintype "passive"))
      (node (ref "R42") (pin "1") (pinfunction "1_1") (pintype "passive"))
    )
    (net (code "48") (name "Net-(Q6-B)") (class "Default")
      (node (ref "Q6") (pin "1") (pinfunction "B_1") (pintype "passive"))
      (node (ref "R35") (pin "2") (pinfunction "2_2") (pintype "passive"))
    )
    (net (code "49") (name "Net-(Q6-C)") (class "Default")
      (node (ref "Q6") (pin "3") (pinfunction "C_3") (pintype "passive"))
      (node (ref "R43") (pin "1") (pinfunction "1_1") (pintype "passive"))
    )
    (net (code "50") (name "Net-(Q7-B)") (class "Default")
      (node (ref "Q7") (pin "1") (pinfunction "B_1") (pintype "passive"))
      (node (ref "R27") (pin "2") (pinfunction "2_2") (pintype "passive"))
    )
    (net (code "51") (name "Net-(Q7-C)") (class "Default")
      (node (ref "Q7") (pin "3") (pinfunction "C_3") (pintype "passive"))
      (node (ref "R44") (pin "1") (pinfunction "1_1") (pintype "passive"))
    )
    (net (code "52") (name "Net-(Q8-B)") (class "Default")
      (node (ref "Q8") (pin "1") (pinfunction "B_1") (pintype "passive"))
      (node (ref "R28") (pin "2") (pinfunction "2_2") (pintype "passive"))
    )
    (net (code "53") (name "Net-(Q8-C)") (class "Default")
      (node (ref "Q8") (pin "3") (pinfunction "C_3") (pintype "passive"))
      (node (ref "R45") (pin "1") (pinfunction "1_1") (pintype "passive"))
    )
    (net (code "54") (name "Net-(Q9-B)") (class "Default")
      (node (ref "Q9") (pin "1") (pinfunction "B_1") (pintype "passive"))
      (node (ref "R26") (pin "2") (pinfunction "2_2") (pintype "passive"))
    )
    (net (code "55") (name "Net-(Q9-C)") (class "Default")
      (node (ref "Q9") (pin "3") (pinfunction "C_3") (pintype "passive"))
      (node (ref "R46") (pin "1") (pinfunction "1_1") (pintype "passive"))
    )
    (net (code "56") (name "Net-(Q10-B)") (class "Default")
      (node (ref "Q10") (pin "1") (pinfunction "B_1") (pintype "passive"))
      (node (ref "R34") (pin "2") (pinfunction "2_2") (pintype "passive"))
    )
    (net (code "57") (name "Net-(Q10-C)") (class "Default")
      (node (ref "Q10") (pin "3") (pinfunction "C_3") (pintype "passive"))
      (node (ref "R47") (pin "1") (pinfunction "1_1") (pintype "passive"))
    )
    (net (code "58") (name "Net-(Q11-B)") (class "Default")
      (node (ref "Q11") (pin "1") (pinfunction "B_1") (pintype "passive"))
      (node (ref "R32") (pin "2") (pinfunction "2_2") (pintype "passive"))
    )
    (net (code "59") (name "Net-(Q11-C)") (class "Default")
      (node (ref "Q11") (pin "3") (pinfunction "C_3") (pintype "passive"))
      (node (ref "R48") (pin "1") (pinfunction "1_1") (pintype "passive"))
    )
    (net (code "60") (name "Net-(Q12-B)") (class "Default")
      (node (ref "Q12") (pin "1") (pinfunction "B_1") (pintype "passive"))
      (node (ref "R33") (pin "2") (pinfunction "2_2") (pintype "passive"))
    )
    (net (code "61") (name "Net-(Q12-C)") (class "Default")
      (node (ref "Q12") (pin "3") (pinfunction "C_3") (pintype "passive"))
      (node (ref "R49") (pin "1") (pinfunction "1_1") (pintype "passive"))
    )
    (net (code "62") (name "Net-(Q13-B)") (class "Default")
      (node (ref "Q13") (pin "1") (pinfunction "B_1") (pintype "passive"))
      (node (ref "R23") (pin "2") (pinfunction "2_2") (pintype "passive"))
    )
    (net (code "63") (name "Net-(Q13-C)") (class "Default")
      (node (ref "Q13") (pin "3") (pinfunction "C_3") (pintype "passive"))
      (node (ref "R50") (pin "1") (pinfunction "1_1") (pintype "passive"))
    )
    (net (code "64") (name "Net-(Q14-B)") (class "Default")
      (node (ref "Q14") (pin "1") (pinfunction "B_1") (pintype "passive"))
      (node (ref "R24") (pin "2") (pinfunction "2_2") (pintype "passive"))
    )
    (net (code "65") (name "Net-(Q14-C)") (class "Default")
      (node (ref "Q14") (pin "3") (pinfunction "C_3") (pintype "passive"))
      (node (ref "R51") (pin "1") (pinfunction "1_1") (pintype "passive"))
    )
    (net (code "66") (name "Net-(Q15-B)") (class "Default")
      (node (ref "Q15") (pin "1") (pinfunction "B_1") (pintype "passive"))
      (node (ref "R25") (pin "2") (pinfunction "2_2") (pintype "passive"))
    )
    (net (code "67") (name "Net-(Q15-C)") (class "Default")
      (node (ref "Q15") (pin "3") (pinfunction "C_3") (pintype "passive"))
      (node (ref "R52") (pin "1") (pinfunction "1_1") (pintype "passive"))
    )
    (net (code "68") (name "Net-(Q16-B)") (class "Default")
      (node (ref "Q16") (pin "1") (pinfunction "B_1") (pintype "passive"))
      (node (ref "R15") (pin "2") (pinfunction "2_2") (pintype "passive"))
    )
    (net (code "69") (name "Net-(Q16-C)") (class "Default")
      (node (ref "Q16") (pin "3") (pinfunction "C_3") (pintype "passive"))
      (node (ref "R53") (pin "2") (pinfunction "2_2") (pintype "passive"))
    )
    (net (code "70") (name "Net-(Q17-B)") (class "Default")
      (node (ref "Q17") (pin "1") (pinfunction "B_1") (pintype "passive"))
      (node (ref "R16") (pin "2") (pinfunction "2_2") (pintype "passive"))
    )
    (net (code "71") (name "Net-(Q17-C)") (class "Default")
      (node (ref "Q17") (pin "3") (pinfunction "C_3") (pintype "passive"))
      (node (ref "R54") (pin "2") (pinfunction "2_2") (pintype "passive"))
    )
    (net (code "72") (name "Net-(Q18-B)") (class "Default")
      (node (ref "Q18") (pin "1") (pinfunction "B_1") (pintype "passive"))
      (node (ref "R14") (pin "2") (pinfunction "2_2") (pintype "passive"))
    )
    (net (code "73") (name "Net-(Q18-C)") (class "Default")
      (node (ref "Q18") (pin "3") (pinfunction "C_3") (pintype "passive"))
      (node (ref "R55") (pin "2") (pinfunction "2_2") (pintype "passive"))
    )
    (net (code "74") (name "Net-(Q19-B)") (class "Default")
      (node (ref "Q19") (pin "1") (pinfunction "B_1") (pintype "passive"))
      (node (ref "R21") (pin "2") (pinfunction "2_2") (pintype "passive"))
    )
    (net (code "75") (name "Net-(Q19-C)") (class "Default")
      (node (ref "Q19") (pin "3") (pinfunction "C_3") (pintype "passive"))
      (node (ref "R56") (pin "2") (pinfunction "2_2") (pintype "passive"))
    )
    (net (code "76") (name "Net-(Q20-B)") (class "Default")
      (node (ref "Q20") (pin "1") (pinfunction "B_1") (pintype "passive"))
      (node (ref "R22") (pin "2") (pinfunction "2_2") (pintype "passive"))
    )
    (net (code "77") (name "Net-(Q20-C)") (class "Default")
      (node (ref "Q20") (pin "3") (pinfunction "C_3") (pintype "passive"))
      (node (ref "R57") (pin "2") (pinfunction "2_2") (pintype "passive"))
    )
    (net (code "78") (name "Net-(Q21-B)") (class "Default")
      (node (ref "Q21") (pin "1") (pinfunction "B_1") (pintype "passive"))
      (node (ref "R20") (pin "2") (pinfunction "2_2") (pintype "passive"))
    )
    (net (code "79") (name "Net-(Q21-C)") (class "Default")
      (node (ref "Q21") (pin "3") (pinfunction "C_3") (pintype "passive"))
      (node (ref "R58") (pin "2") (pinfunction "2_2") (pintype "passive"))
    )
    (net (code "80") (name "Net-(Q22-B)") (class "Default")
      (node (ref "Q22") (pin "1") (pinfunction "B_1") (pintype "passive"))
      (node (ref "R12") (pin "2") (pinfunction "2_2") (pintype "passive"))
    )
    (net (code "81") (name "Net-(Q22-C)") (class "Default")
      (node (ref "Q22") (pin "3") (pinfunction "C_3") (pintype "passive"))
      (node (ref "R59") (pin "2") (pinfunction "2_2") (pintype "passive"))
    )
    (net (code "82") (name "Net-(Q23-B)") (class "Default")
      (node (ref "Q23") (pin "1") (pinfunction "B_1") (pintype "passive"))
      (node (ref "R13") (pin "2") (pinfunction "2_2") (pintype "passive"))
    )
    (net (code "83") (name "Net-(Q23-C)") (class "Default")
      (node (ref "Q23") (pin "3") (pinfunction "C_3") (pintype "passive"))
      (node (ref "R60") (pin "2") (pinfunction "2_2") (pintype "passive"))
    )
    (net (code "84") (name "Net-(Q24-B)") (class "Default")
      (node (ref "Q24") (pin "1") (pinfunction "B_1") (pintype "passive"))
      (node (ref "R11") (pin "2") (pinfunction "2_2") (pintype "passive"))
    )
    (net (code "85") (name "Net-(Q24-C)") (class "Default")
      (node (ref "Q24") (pin "3") (pinfunction "C_3") (pintype "passive"))
      (node (ref "R61") (pin "2") (pinfunction "2_2") (pintype "passive"))
    )
    (net (code "86") (name "Net-(Q25-B)") (class "Default")
      (node (ref "Q25") (pin "1") (pinfunction "B_1") (pintype "passive"))
      (node (ref "R8") (pin "2") (pinfunction "2_2") (pintype "passive"))
    )
    (net (code "87") (name "Net-(Q25-C)") (class "Default")
      (node (ref "Q25") (pin "3") (pinfunction "C_3") (pintype "passive"))
      (node (ref "R62") (pin "2") (pinfunction "2_2") (pintype "passive"))
    )
    (net (code "88") (name "Net-(Q26-B)") (class "Default")
      (node (ref "Q26") (pin "1") (pinfunction "B_1") (pintype "passive"))
      (node (ref "R9") (pin "2") (pinfunction "2_2") (pintype "passive"))
    )
    (net (code "89") (name "Net-(Q26-C)") (class "Default")
      (node (ref "Q26") (pin "3") (pinfunction "C_3") (pintype "passive"))
      (node (ref "R63") (pin "2") (pinfunction "2_2") (pintype "passive"))
    )
    (net (code "90") (name "Net-(Q27-B)") (class "Default")
      (node (ref "Q27") (pin "1") (pinfunction "B_1") (pintype "passive"))
      (node (ref "R10") (pin "2") (pinfunction "2_2") (pintype "passive"))
    )
    (net (code "91") (name "Net-(Q27-C)") (class "Default")
      (node (ref "Q27") (pin "3") (pinfunction "C_3") (pintype "passive"))
      (node (ref "R64") (pin "2") (pinfunction "2_2") (pintype "passive"))
    )
    (net (code "92") (name "Net-(Q28-B)") (class "Default")
      (node (ref "Q28") (pin "1") (pinfunction "B_1") (pintype "passive"))
      (node (ref "R18") (pin "2") (pinfunction "2_2") (pintype "passive"))
    )
    (net (code "93") (name "Net-(Q28-C)") (class "Default")
      (node (ref "Q28") (pin "3") (pinfunction "C_3") (pintype "passive"))
      (node (ref "R65") (pin "2") (pinfunction "2_2") (pintype "passive"))
    )
    (net (code "94") (name "Net-(Q29-B)") (class "Default")
      (node (ref "Q29") (pin "1") (pinfunction "B_1") (pintype "passive"))
      (node (ref "R17") (pin "2") (pinfunction "2_2") (pintype "passive"))
    )
    (net (code "95") (name "Net-(Q29-C)") (class "Default")
      (node (ref "Q29") (pin "3") (pinfunction "C_3") (pintype "passive"))
      (node (ref "R66") (pin "2") (pinfunction "2_2") (pintype "passive"))
    )
    (net (code "96") (name "Net-(Q30-B)") (class "Default")
      (node (ref "Q30") (pin "1") (pinfunction "B_1") (pintype "passive"))
      (node (ref "R19") (pin "2") (pinfunction "2_2") (pintype "passive"))
    )
    (net (code "97") (name "Net-(Q30-C)") (class "Default")
      (node (ref "Q30") (pin "3") (pinfunction "C_3") (pintype "passive"))
      (node (ref "R67") (pin "2") (pinfunction "2_2") (pintype "passive"))
    )
    (net (code "98") (name "Net-(U1-FB)") (class "Default")
      (node (ref "C3") (pin "2") (pinfunction "2_2") (pintype "passive"))
      (node (ref "U1") (pin "1") (pinfunction "FB_1") (pintype "passive"))
    )
    (net (code "99") (name "Net-(U1-INV)") (class "Default")
      (node (ref "R3") (pin "1") (pinfunction "1_1") (pintype "passive"))
      (node (ref "R4") (pin "2") (pinfunction "2_2") (pintype "passive"))
      (node (ref "R5") (pin "1") (pinfunction "1_1") (pintype "passive"))
      (node (ref "R6") (pin "1") (pinfunction "1_1") (pintype "passive"))
      (node (ref "U1") (pin "2") (pinfunction "INV_2") (pintype "passive"))
    )
    (net (code "100") (name "Net-(U1-RT)") (class "Default")
      (node (ref "R2") (pin "1") (pinfunction "1_1") (pintype "passive"))
      (node (ref "U1") (pin "16") (pinfunction "RT_16") (pintype "passive"))
    )
    (net (code "101") (name "Net-(U1-STB)") (class "Default")
      (node (ref "R1") (pin "2") (pinfunction "2_2") (pintype "passive"))
      (node (ref "U1") (pin "15") (pinfunction "STB_15") (pintype "passive"))
    )
    (net (code "102") (name "Net-(U3-RA4)") (class "Default")
      (node (ref "U3") (pin "3") (pinfunction "RA4_3") (pintype "passive"))
      (node (ref "U4") (pin "14") (pinfunction "IOB_32A_SPI_SO_14") (pintype "passive"))
    )
    (net (code "103") (name "Net-(U3-RC0)") (class "Default")
      (node (ref "S1") (pin "4") (pinfunction "4_4") (pintype "passive"))
      (node (ref "U3") (pin "10") (pinfunction "RC0_10") (pintype "passive"))
    )
    (net (code "104") (name "Net-(U3-RC1)") (class "Default")
      (node (ref "U3") (pin "9") (pinfunction "RC1_9") (pintype "passive"))
      (node (ref "U4") (pin "7") (pinfunction "CDONE_7") (pintype "passive"))
    )
    (net (code "105") (name "Net-(U3-RC2)") (class "Default")
      (node (ref "U3") (pin "8") (pinfunction "RC2_8") (pintype "passive"))
      (node (ref "U4") (pin "8") (pinfunction "CRESET_B_8") (pintype "passive"))
    )
    (net (code "106") (name "Net-(U3-RC3)") (class "Default")
      (node (ref "U3") (pin "7") (pinfunction "RC3_7") (pintype "passive"))
      (node (ref "U4") (pin "17") (pinfunction "IOB_33B_SPI_SI_17") (pintype "passive"))
    )
    (net (code "107") (name "Net-(U3-RC4)") (class "Default")
      (node (ref "U3") (pin "6") (pinfunction "RC4_6") (pintype "passive"))
      (node (ref "U4") (pin "16") (pinfunction "IOB_35B_SPI_CSN_16") (pintype "passive"))
    )
    (net (code "108") (name "Net-(U3-RC5)") (class "Default")
      (node (ref "U3") (pin "5") (pinfunction "RC5_5") (pintype "passive"))
      (node (ref "U4") (pin "15") (pinfunction "IOB_34A_SPI_SCK_15") (pintype "passive"))
    )
    (net (code "109") (name "Net-(U3-~{MCLR})") (class "Default")
      (node (ref "R7") (pin "2") (pinfunction "2_2") (pintype "passive"))
      (node (ref "U3") (pin "4") (pinfunction "~{MCLR}_4") (pintype "passive"))
    )
    (net (code "110") (name "Net-(U4-IOB_0A)") (class "Default")
      (node (ref "R31") (pin "1") (pinfunction "1_1") (pintype "passive"))
      (node (ref "U4") (pin "46") (pinfunction "IOB_0A_46") (pintype "passive"))
    )
    (net (code "111") (name "Net-(U4-IOB_2A)") (class "Default")
      (node (ref "R32") (pin "1") (pinfunction "1_1") (pintype "passive"))
      (node (ref "U4") (pin "47") (pinfunction "IOB_2A_47") (pintype "passive"))
    )
    (net (code "112") (name "Net-(U4-IOB_3B_G6)") (class "Default")
      (node (ref "R29") (pin "1") (pinfunction "1_1") (pintype "passive"))
      (node (ref "U4") (pin "44") (pinfunction "IOB_3B_G6_44") (pintype "passive"))
    )
    (net (code "113") (name "Net-(U4-IOB_4A)") (class "Default")
      (node (ref "R33") (pin "1") (pinfunction "1_1") (pintype "passive"))
      (node (ref "U4") (pin "48") (pinfunction "IOB_4A_48") (pintype "passive"))
    )
    (net (code "114") (name "Net-(U4-IOB_5B)") (class "Default")
      (node (ref "R30") (pin "1") (pinfunction "1_1") (pintype "passive"))
      (node (ref "U4") (pin "45") (pinfunction "IOB_5B_45") (pintype "passive"))
    )
    (net (code "115") (name "Net-(U4-IOB_6A)") (class "Default")
      (node (ref "R34") (pin "1") (pinfunction "1_1") (pintype "passive"))
      (node (ref "U4") (pin "2") (pinfunction "IOB_6A_2") (pintype "passive"))
    )
    (net (code "116") (name "Net-(U4-IOB_8A)") (class "Default")
      (node (ref "R36") (pin "1") (pinfunction "1_1") (pintype "passive"))
      (node (ref "U4") (pin "4") (pinfunction "IOB_8A_4") (pintype "passive"))
    )
    (net (code "117") (name "Net-(U4-IOB_9B)") (class "Default")
      (node (ref "R35") (pin "1") (pinfunction "1_1") (pintype "passive"))
      (node (ref "U4") (pin "3") (pinfunction "IOB_9B_3") (pintype "passive"))
    )
    (net (code "118") (name "Net-(U4-IOB_13B)") (class "Default")
      (node (ref "R37") (pin "1") (pinfunction "1_1") (pintype "passive"))
      (node (ref "U4") (pin "6") (pinfunction "IOB_13B_6") (pintype "passive"))
    )
    (net (code "119") (name "Net-(U4-IOB_23B)") (class "Default")
      (node (ref "R8") (pin "1") (pinfunction "1_1") (pintype "passive"))
      (node (ref "U4") (pin "21") (pinfunction "IOB_23B_21") (pintype "passive"))
    )
    (net (code "120") (name "Net-(U4-IOB_25B_G3)") (class "Default")
      (node (ref "R19") (pin "1") (pinfunction "1_1") (pintype "passive"))
      (node (ref "U4") (pin "20") (pinfunction "IOB_25B_G3_20") (pintype "passive"))
    )
    (net (code "121") (name "Net-(U4-IOB_29B)") (class "Default")
      (node (ref "R18") (pin "1") (pinfunction "1_1") (pintype "passive"))
      (node (ref "U4") (pin "19") (pinfunction "IOB_29B_19") (pintype "passive"))
    )
    (net (code "122") (name "Net-(U4-IOB_31B)") (class "Default")
      (node (ref "R17") (pin "1") (pinfunction "1_1") (pintype "passive"))
      (node (ref "U4") (pin "18") (pinfunction "IOB_31B_18") (pintype "passive"))
    )
    (net (code "123") (name "Net-(U4-IOT_37A)") (class "Default")
      (node (ref "R9") (pin "1") (pinfunction "1_1") (pintype "passive"))
      (node (ref "U4") (pin "23") (pinfunction "IOT_37A_23") (pintype "passive"))
    )
    (net (code "124") (name "Net-(U4-IOT_38B)") (class "Default")
      (node (ref "R12") (pin "1") (pinfunction "1_1") (pintype "passive"))
      (node (ref "U4") (pin "27") (pinfunction "IOT_38B_27") (pintype "passive"))
    )
    (net (code "125") (name "Net-(U4-IOT_41A)") (class "Default")
      (node (ref "R13") (pin "1") (pinfunction "1_1") (pintype "passive"))
      (node (ref "U4") (pin "28") (pinfunction "IOT_41A_28") (pintype "passive"))
    )
    (net (code "126") (name "Net-(U4-IOT_42B)") (class "Default")
      (node (ref "R14") (pin "1") (pinfunction "1_1") (pintype "passive"))
      (node (ref "U4") (pin "31") (pinfunction "IOT_42B_31") (pintype "passive"))
    )
    (net (code "127") (name "Net-(U4-IOT_43A)") (class "Default")
      (node (ref "R15") (pin "1") (pinfunction "1_1") (pintype "passive"))
      (node (ref "U4") (pin "32") (pinfunction "IOT_43A_32") (pintype "passive"))
    )
    (net (code "128") (name "Net-(U4-IOT_44B)") (class "Default")
      (node (ref "R16") (pin "1") (pinfunction "1_1") (pintype "passive"))
      (node (ref "U4") (pin "34") (pinfunction "IOT_44B_34") (pintype "passive"))
    )
    (net (code "129") (name "Net-(U4-IOT_45A_G1)") (class "Default")
      (node (ref "R22") (pin "1") (pinfunction "1_1") (pintype "passive"))
      (node (ref "U4") (pin "37") (pinfunction "IOT_45A_G1_37") (pintype "passive"))
    )
    (net (code "130") (name "Net-(U4-IOT_46B_G0)") (class "Default")
      (node (ref "R20") (pin "1") (pinfunction "1_1") (pintype "passive"))
      (node (ref "U4") (pin "35") (pinfunction "IOT_46B_G0_35") (pintype "passive"))
    )
    (net (code "131") (name "Net-(U4-IOT_48B)") (class "Default")
      (node (ref "R21") (pin "1") (pinfunction "1_1") (pintype "passive"))
      (node (ref "U4") (pin "36") (pinfunction "IOT_48B_36") (pintype "passive"))
    )
    (net (code "132") (name "Net-(U4-IOT_49A)") (class "Default")
      (node (ref "R28") (pin "1") (pinfunction "1_1") (pintype "passive"))
      (node (ref "U4") (pin "43") (pinfunction "IOT_49A_43") (pintype "passive"))
    )
    (net (code "133") (name "Net-(U4-IOT_50B)") (class "Default")
      (node (ref "R23") (pin "1") (pinfunction "1_1") (pintype "passive"))
      (node (ref "U4") (pin "38") (pinfunction "IOT_50B_38") (pintype "passive"))
    )
    (net (code "134") (name "Net-(U4-IOT_51A)") (class "Default")
      (node (ref "R27") (pin "1") (pinfunction "1_1") (pintype "passive"))
      (node (ref "U4") (pin "42") (pinfunction "IOT_51A_42") (pintype "passive"))
    )
    (net (code "135") (name "Net-(U4-IOT__36B)") (class "Default")
      (node (ref "R10") (pin "1") (pinfunction "1_1") (pintype "passive"))
      (node (ref "U4") (pin "25") (pinfunction "IOT__36B_25") (pintype "passive"))
    )
    (net (code "136") (name "Net-(U4-IOT__39A)") (class "Default")
      (node (ref "R11") (pin "1") (pinfunction "1_1") (pintype "passive"))
      (node (ref "U4") (pin "26") (pinfunction "IOT__39A_26") (pintype "passive"))
    )
    (net (code "137") (name "Net-(U4-RGB0)") (class "Default")
      (node (ref "R26") (pin "1") (pinfunction "1_1") (pintype "passive"))
      (node (ref "U4") (pin "41") (pinfunction "RGB0_41") (pintype "passive"))
    )
    (net (code "138") (name "Net-(U4-RGB1)") (class "Default")
      (node (ref "R25") (pin "1") (pinfunction "1_1") (pintype "passive"))
      (node (ref "U4") (pin "40") (pinfunction "RGB1_40") (pintype "passive"))
    )
    (net (code "139") (name "Net-(U4-RGB2)") (class "Default")
      (node (ref "R24") (pin "1") (pinfunction "1_1") (pintype "passive"))
      (node (ref "U4") (pin "39") (pinfunction "RGB2_39") (pintype "passive"))
    )
    (net (code "140") (name "VIN") (class "Default")
      (node (ref "C1") (pin "1") (pinfunction "1_1") (pintype "passive"))
      (node (ref "C15") (pin "1") (pinfunction "A_1") (pintype "passive"))
      (node (ref "C2") (pin "1") (pinfunction "1_1") (pintype "passive"))
      (node (ref "D1") (pin "1") (pinfunction "+_1") (pintype "passive"))
      (node (ref "R1") (pin "1") (pinfunction "1_1") (pintype "passive"))
      (node (ref "U1") (pin "12") (pinfunction "PVCC_12") (pintype "passive"))
      (node (ref "U1") (pin "13") (pinfunction "PVCC_13") (pintype "passive"))
      (node (ref "U1") (pin "14") (pinfunction "VCC_14") (pintype "passive"))
      (node (ref "Z1") (pin "1") (pinfunction "K_1") (pintype "passive"))
    )
    (net (code "141") (name "unconnected-(D1-~-Pad3)") (class "Default")
      (node (ref "D1") (pin "3") (pinfunction "~_3") (pintype "passive"))
    )
    (net (code "142") (name "unconnected-(D1-~-Pad4)") (class "Default")
      (node (ref "D1") (pin "4") (pinfunction "~_4") (pintype "passive"))
    )
    (net (code "143") (name "unconnected-(S1-Pad1)") (class "Default")
      (node (ref "S1") (pin "1") (pinfunction "1_1") (pintype "passive"))
    )
    (net (code "144") (name "unconnected-(S1-Pad3)") (class "Default")
      (node (ref "S1") (pin "3") (pinfunction "3_3") (pintype "passive"))
    )
    (net (code "145") (name "unconnected-(U3-RA0{slash}ICSPDAT-Pad13)") (class "Default")
      (node (ref "U3") (pin "13") (pinfunction "RA0/ICSPDAT_13") (pintype "passive"))
    )
    (net (code "146") (name "unconnected-(U3-RA1{slash}ICSPCLK-Pad12)") (class "Default")
      (node (ref "U3") (pin "12") (pinfunction "RA1/ICSPCLK_12") (pintype "passive"))
    )
    (net (code "147") (name "unconnected-(U3-RA2-Pad11)") (class "Default")
      (node (ref "U3") (pin "11") (pinfunction "RA2_11") (pintype "passive"))
    )
    (net (code "148") (name "unconnected-(U3-RA5-Pad2)") (class "Default")
      (node (ref "U3") (pin "2") (pinfunction "RA5_2") (pintype "passive"))
    )
    (net (code "149") (name "unconnected-(U4-IOB_16A-Pad9)") (class "Default")
      (node (ref "U4") (pin "9") (pinfunction "IOB_16A_9") (pintype "passive"))
    )
    (net (code "150") (name "unconnected-(U4-IOB_18A-Pad10)") (class "Default")
      (node (ref "U4") (pin "10") (pinfunction "IOB_18A_10") (pintype "passive"))
    )
    (net (code "151") (name "unconnected-(U4-IOB_20A-Pad11)") (class "Default")
      (node (ref "U4") (pin "11") (pinfunction "IOB_20A_11") (pintype "passive"))
    )
    (net (code "152") (name "unconnected-(U4-IOB_22A-Pad12)") (class "Default")
      (node (ref "U4") (pin "12") (pinfunction "IOB_22A_12") (pintype "passive"))
    )
    (net (code "153") (name "unconnected-(U4-IOB_24A-Pad13)") (class "Default")
      (node (ref "U4") (pin "13") (pinfunction "IOB_24A_13") (pintype "passive"))
    )
  )
)
